# roomba.net
KiCad netlist of a schematic drawn in EAGLE
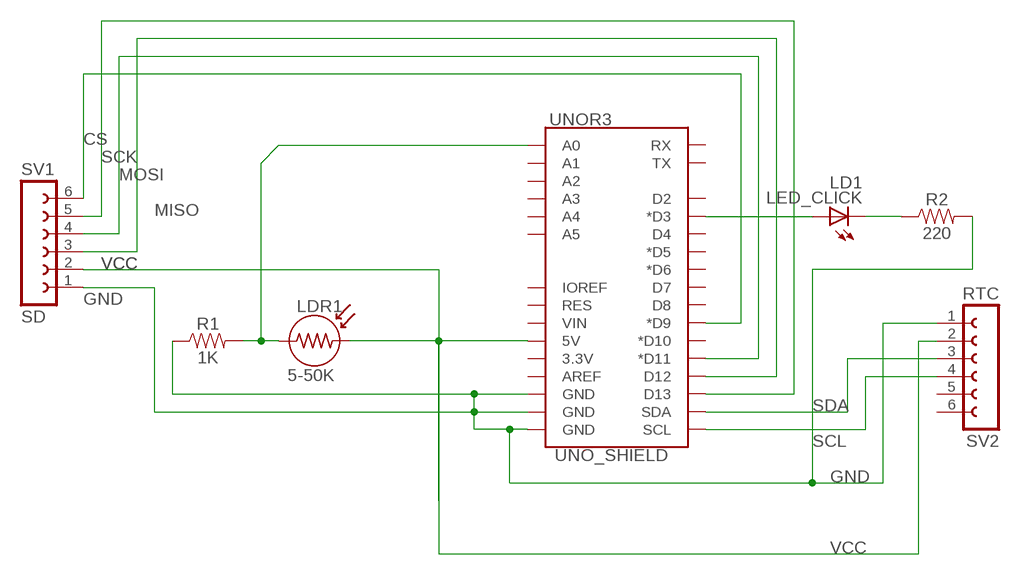
[diagram p0: schematic, sheet 1]

(export (version "E")
  (design (tool "Eeschema 10.0.6"))
  (components
    (comp (ref "LDR1")
      (value "5-50K")
      (footprint "eagle-import:LDR")
      (libsource (lib "eagle-import") (part "LDR"))
    )
    (comp (ref "LED_CLICK")
      (value "LD1")
      (footprint "eagle-import:LED3MM")
      (libsource (lib "eagle-import") (part "LED3MM"))
    )
    (comp (ref "R1")
      (value "1K")
      (footprint "eagle-import:AXIAL-0.3")
      (fields (field (name "SPICEPREFIX") "R"))
      (libsource (lib "eagle-import") (part "1KOHM-HORIZ-1/4W-1%"))
    )
    (comp (ref "R2")
      (value "220")
      (footprint "eagle-import:AXIAL-0.3")
      (fields (field (name "SPICEPREFIX") "R"))
      (libsource (lib "eagle-import") (part "1KOHM-HORIZ-1/4W-1%"))
    )
    (comp (ref "SV1")
      (value "SD")
      (footprint "eagle-import:FE06")
      (libsource (lib "eagle-import") (part "FE06-1"))
    )
    (comp (ref "SV2")
      (value "RTC")
      (footprint "eagle-import:FE06W")
      (libsource (lib "eagle-import") (part "FE06W"))
    )
    (comp (ref "UNOR3")
      (value "UNO_SHIELD")
      (footprint "eagle-import:UNO_R3_SHIELD_NOLABELS")
      (libsource (lib "eagle-import") (part "ARDUINO_UNO_R3_SHIELDNOLABELS"))
    )
  )
  (nets
    (net (code "1") (name "/CS") (class "Default")
      (node (ref "SV1") (pin "6") (pinfunction "6_6") (pintype "passive"))
      (node (ref "UNOR3") (pin "D9") (pinfunction "*D9_D9") (pintype "bidirectional"))
    )
    (net (code "2") (name "/GND") (class "Default")
      (node (ref "R1") (pin "P$1") (pinfunction "1_P$1") (pintype "passive"))
      (node (ref "R2") (pin "P$2") (pinfunction "2_P$2") (pintype "passive"))
      (node (ref "SV1") (pin "1") (pinfunction "1_1") (pintype "passive"))
      (node (ref "SV2") (pin "1") (pinfunction "1_1") (pintype "passive"))
      (node (ref "UNOR3") (pin "GND@0") (pinfunction "GND_GND@0") (pintype "bidirectional"))
      (node (ref "UNOR3") (pin "GND@1") (pinfunction "GND_GND@1") (pintype "bidirectional"))
      (node (ref "UNOR3") (pin "GND@2") (pinfunction "GND_GND@2") (pintype "bidirectional"))
    )
    (net (code "3") (name "/MISO") (class "Default")
      (node (ref "SV1") (pin "3") (pinfunction "3_3") (pintype "passive"))
      (node (ref "UNOR3") (pin "D12") (pinfunction "D12_D12") (pintype "bidirectional"))
    )
    (net (code "4") (name "/MOSI") (class "Default")
      (node (ref "SV1") (pin "4") (pinfunction "4_4") (pintype "passive"))
      (node (ref "UNOR3") (pin "D11") (pinfunction "*D11_D11") (pintype "bidirectional"))
    )
    (net (code "5") (name "/SCK") (class "Default")
      (node (ref "SV1") (pin "5") (pinfunction "5_5") (pintype "passive"))
      (node (ref "UNOR3") (pin "D13") (pinfunction "D13_D13") (pintype "bidirectional"))
    )
    (net (code "6") (name "/SCL") (class "Default")
      (node (ref "SV2") (pin "4") (pinfunction "4_4") (pintype "passive"))
      (node (ref "UNOR3") (pin "SCL") (pinfunction "SCL_SCL") (pintype "bidirectional"))
    )
    (net (code "7") (name "/SDA") (class "Default")
      (node (ref "SV2") (pin "3") (pinfunction "3_3") (pintype "passive"))
      (node (ref "UNOR3") (pin "SDA") (pinfunction "SDA_SDA") (pintype "bidirectional"))
    )
    (net (code "8") (name "/VCC") (class "Default")
      (node (ref "LDR1") (pin "2") (pinfunction "2_2") (pintype "passive"))
      (node (ref "SV1") (pin "2") (pinfunction "2_2") (pintype "passive"))
      (node (ref "SV2") (pin "2") (pinfunction "2_2") (pintype "passive"))
      (node (ref "UNOR3") (pin "5V") (pinfunction "5V_5V") (pintype "bidirectional"))
    )
    (net (code "9") (name "Net-(LED_CLICK-C)") (class "Default")
      (node (ref "LED_CLICK") (pin "K") (pinfunction "C_K") (pintype "passive"))
      (node (ref "R2") (pin "P$1") (pinfunction "1_P$1") (pintype "passive"))
    )
    (net (code "10") (name "Net-(R1-2)") (class "Default")
      (node (ref "LDR1") (pin "1") (pinfunction "1_1") (pintype "passive"))
      (node (ref "R1") (pin "P$2") (pinfunction "2_P$2") (pintype "passive"))
      (node (ref "UNOR3") (pin "A0") (pinfunction "A0_A0") (pintype "bidirectional"))
    )
    (net (code "11") (name "Net-(UNOR3-*D3)") (class "Default")
      (node (ref "LED_CLICK") (pin "A") (pinfunction "A_A") (pintype "passive"))
      (node (ref "UNOR3") (pin "D3") (pinfunction "*D3_D3") (pintype "bidirectional"))
    )
    (net (code "12") (name "unconnected-(SV2-Pad5)") (class "Default")
      (node (ref "SV2") (pin "5") (pinfunction "5_5") (pintype "passive"))
    )
    (net (code "13") (name "unconnected-(SV2-Pad6)") (class "Default")
      (node (ref "SV2") (pin "6") (pinfunction "6_6") (pintype "passive"))
    )
    (net (code "14") (name "unconnected-(UNOR3-*D5-PadD5)") (class "Default")
      (node (ref "UNOR3") (pin "D5") (pinfunction "*D5_D5") (pintype "bidirectional"))
    )
    (net (code "15") (name "unconnected-(UNOR3-*D6-PadD6)") (class "Default")
      (node (ref "UNOR3") (pin "D6") (pinfunction "*D6_D6") (pintype "bidirectional"))
    )
    (net (code "16") (name "unconnected-(UNOR3-*D10-PadD10)") (class "Default")
      (node (ref "UNOR3") (pin "D10") (pinfunction "*D10_D10") (pintype "bidirectional"))
    )
    (net (code "17") (name "unconnected-(UNOR3-Pad3.3V)") (class "Default")
      (node (ref "UNOR3") (pin "3.3V") (pinfunction "3.3V_3.3V") (pintype "bidirectional"))
    )
    (net (code "18") (name "unconnected-(UNOR3-PadA1)") (class "Default")
      (node (ref "UNOR3") (pin "A1") (pinfunction "A1_A1") (pintype "bidirectional"))
    )
    (net (code "19") (name "unconnected-(UNOR3-PadA2)") (class "Default")
      (node (ref "UNOR3") (pin "A2") (pinfunction "A2_A2") (pintype "bidirectional"))
    )
    (net (code "20") (name "unconnected-(UNOR3-PadA3)") (class "Default")
      (node (ref "UNOR3") (pin "A3") (pinfunction "A3_A3") (pintype "bidirectional"))
    )
    (net (code "21") (name "unconnected-(UNOR3-PadA4)") (class "Default")
      (node (ref "UNOR3") (pin "A4") (pinfunction "A4_A4") (pintype "bidirectional"))
    )
    (net (code "22") (name "unconnected-(UNOR3-PadA5)") (class "Default")
      (node (ref "UNOR3") (pin "A5") (pinfunction "A5_A5") (pintype "bidirectional"))
    )
    (net (code "23") (name "unconnected-(UNOR3-PadAREF)") (class "Default")
      (node (ref "UNOR3") (pin "AREF") (pinfunction "AREF_AREF") (pintype "bidirectional"))
    )
    (net (code "24") (name "unconnected-(UNOR3-PadD2)") (class "Default")
      (node (ref "UNOR3") (pin "D2") (pinfunction "D2_D2") (pintype "bidirectional"))
    )
    (net (code "25") (name "unconnected-(UNOR3-PadD4)") (class "Default")
      (node (ref "UNOR3") (pin "D4") (pinfunction "D4_D4") (pintype "bidirectional"))
    )
    (net (code "26") (name "unconnected-(UNOR3-PadD7)") (class "Default")
      (node (ref "UNOR3") (pin "D7") (pinfunction "D7_D7") (pintype "bidirectional"))
    )
    (net (code "27") (name "unconnected-(UNOR3-PadD8)") (class "Default")
      (node (ref "UNOR3") (pin "D8") (pinfunction "D8_D8") (pintype "bidirectional"))
    )
    (net (code "28") (name "unconnected-(UNOR3-PadIOREF)") (class "Default")
      (node (ref "UNOR3") (pin "IOREF") (pinfunction "IOREF_IOREF") (pintype "bidirectional"))
    )
    (net (code "29") (name "unconnected-(UNOR3-PadRES)") (class "Default")
      (node (ref "UNOR3") (pin "RES") (pinfunction "RES_RES") (pintype "bidirectional"))
    )
    (net (code "30") (name "unconnected-(UNOR3-PadRX)") (class "Default")
      (node (ref "UNOR3") (pin "RX") (pinfunction "RX_RX") (pintype "bidirectional"))
    )
    (net (code "31") (name "unconnected-(UNOR3-PadTX)") (class "Default")
      (node (ref "UNOR3") (pin "TX") (pinfunction "TX_TX") (pintype "bidirectional"))
    )
    (net (code "32") (name "unconnected-(UNOR3-PadVIN)") (class "Default")
      (node (ref "UNOR3") (pin "VIN") (pinfunction "VIN_VIN") (pintype "bidirectional"))
    )
  )
)
